# Mini_Converter_2024-05-02.net
KiCad netlist of a schematic drawn in Altium Designer
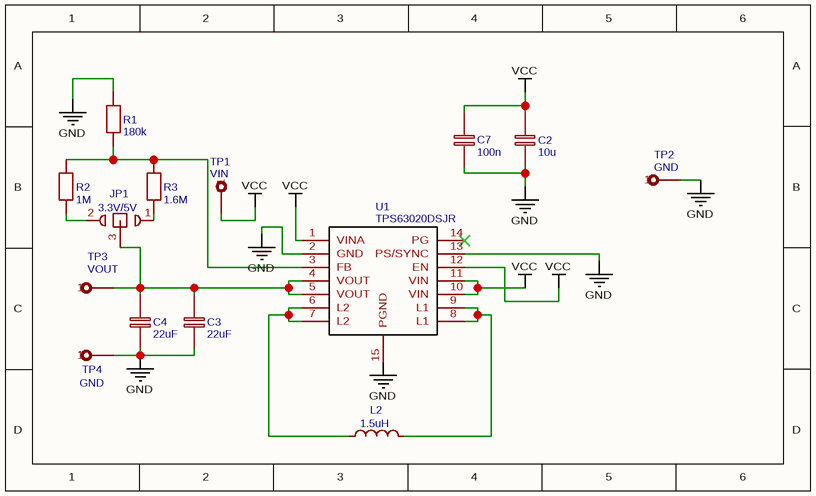
[diagram p0: Mini_Converter_2024-05-02.schdoc]

(export (version "E")
  (design (tool "Eeschema 10.0.6"))
  (components
    (comp (ref "C2")
      (value "10u")
      (fields (field (name "CONTRIBUTOR") "LCEDA_Lib"))
      (libsource (lib "altium-import") (part "root_1_10u_"))
    )
    (comp (ref "C3")
      (value "22uF")
      (fields (field (name "CONTRIBUTOR") "LCEDA_Lib"))
      (libsource (lib "altium-import") (part "root_1_22uF_"))
    )
    (comp (ref "C4")
      (value "22uF")
      (fields (field (name "CONTRIBUTOR") "LCEDA_Lib"))
      (libsource (lib "altium-import") (part "root_1_22uF_"))
    )
    (comp (ref "C7")
      (value "100n")
      (fields (field (name "CONTRIBUTOR") "LCEDA_Lib"))
      (libsource (lib "altium-import") (part "root_1_100n_"))
    )
    (comp (ref "JP1")
      (value "3.3V/5V")
      (fields (field (name "CONTRIBUTOR") "leif"))
      (libsource (lib "altium-import") (part "root_2_3.3V/5V_"))
    )
    (comp (ref "L2")
      (value "1.5uH")
      (fields (field (name "MANUFACTURER PART") "78438336100") (field (name "CONTRIBUTOR") "LCSC"))
      (libsource (lib "altium-import") (part "root_0_1.5uH_"))
    )
    (comp (ref "R1")
      (value "180k")
      (fields (field (name "CONTRIBUTOR") "LCEDA_Lib"))
      (libsource (lib "altium-import") (part "root_1_180k_"))
    )
    (comp (ref "R2")
      (value "1M")
      (fields (field (name "CONTRIBUTOR") "LCEDA_Lib"))
      (libsource (lib "altium-import") (part "root_1_1M_"))
    )
    (comp (ref "R3")
      (value "1.6M")
      (fields (field (name "CONTRIBUTOR") "LCEDA_Lib"))
      (libsource (lib "altium-import") (part "root_1_1.6M_"))
    )
    (comp (ref "TP1") (value "VIN") (libsource (lib "altium-import") (part "root_3_VIN_")))
    (comp (ref "TP2") (value "GND") (libsource (lib "altium-import") (part "root_0_GND_")))
    (comp (ref "TP3") (value "VOUT") (libsource (lib "altium-import") (part "root_0_VOUT_")))
    (comp (ref "TP4") (value "GND") (libsource (lib "altium-import") (part "root_0_GND_")))
    (comp (ref "U1")
      (value "TPS63020DSJR")
      (fields (field (name "MANUFACTURER") "TI(德州仪器)"))
      (libsource (lib "altium-import") (part "root_0_TPS63020DSJR_"))
    )
  )
  (nets
    (net (code "1") (name "GND") (class "Default")
      (node (ref "C2") (pin "1") (pinfunction "1_1") (pintype "passive"))
      (node (ref "C3") (pin "1") (pinfunction "1_1") (pintype "passive"))
      (node (ref "C4") (pin "1") (pinfunction "1_1") (pintype "passive"))
      (node (ref "C7") (pin "1") (pinfunction "1_1") (pintype "passive"))
      (node (ref "R1") (pin "2") (pinfunction "2_2") (pintype "passive"))
      (node (ref "TP2") (pin "1") (pinfunction "1_1") (pintype "passive"))
      (node (ref "TP4") (pin "1") (pinfunction "1_1") (pintype "passive"))
      (node (ref "U1") (pin "13") (pinfunction "PS/SYNC_13") (pintype "passive"))
      (node (ref "U1") (pin "15") (pinfunction "PGND_15") (pintype "passive"))
      (node (ref "U1") (pin "2") (pinfunction "GND_2") (pintype "passive"))
    )
    (net (code "2") (name "Net-(C3-Pad2)") (class "Default")
      (node (ref "C3") (pin "2") (pinfunction "2_2") (pintype "passive"))
      (node (ref "C4") (pin "2") (pinfunction "2_2") (pintype "passive"))
      (node (ref "JP1") (pin "3") (pinfunction "3_3") (pintype "passive"))
      (node (ref "TP3") (pin "1") (pinfunction "1_1") (pintype "passive"))
      (node (ref "U1") (pin "4") (pinfunction "VOUT_4") (pintype "passive"))
      (node (ref "U1") (pin "5") (pinfunction "VOUT_5") (pintype "passive"))
    )
    (net (code "3") (name "Net-(JP1-Pad1)") (class "Default")
      (node (ref "JP1") (pin "1") (pinfunction "1_1") (pintype "passive"))
      (node (ref "R3") (pin "1") (pinfunction "1_1") (pintype "passive"))
    )
    (net (code "4") (name "Net-(JP1-Pad2)") (class "Default")
      (node (ref "JP1") (pin "2") (pinfunction "2_2") (pintype "passive"))
      (node (ref "R2") (pin "1") (pinfunction "1_1") (pintype "passive"))
    )
    (net (code "5") (name "Net-(L2-Pad1)") (class "Default")
      (node (ref "L2") (pin "1") (pinfunction "1_1") (pintype "passive"))
      (node (ref "U1") (pin "6") (pinfunction "L2_6") (pintype "passive"))
      (node (ref "U1") (pin "7") (pinfunction "L2_7") (pintype "passive"))
    )
    (net (code "6") (name "Net-(L2-Pad2)") (class "Default")
      (node (ref "L2") (pin "2") (pinfunction "2_2") (pintype "passive"))
      (node (ref "U1") (pin "8") (pinfunction "L1_8") (pintype "passive"))
      (node (ref "U1") (pin "9") (pinfunction "L1_9") (pintype "passive"))
    )
    (net (code "7") (name "Net-(U1-FB)") (class "Default")
      (node (ref "R1") (pin "1") (pinfunction "1_1") (pintype "passive"))
      (node (ref "R2") (pin "2") (pinfunction "2_2") (pintype "passive"))
      (node (ref "R3") (pin "2") (pinfunction "2_2") (pintype "passive"))
      (node (ref "U1") (pin "3") (pinfunction "FB_3") (pintype "passive"))
    )
    (net (code "8") (name "VCC") (class "Default")
      (node (ref "C2") (pin "2") (pinfunction "2_2") (pintype "passive"))
      (node (ref "C7") (pin "2") (pinfunction "2_2") (pintype "passive"))
      (node (ref "TP1") (pin "1") (pinfunction "1_1") (pintype "passive"))
      (node (ref "U1") (pin "1") (pinfunction "VINA_1") (pintype "passive"))
      (node (ref "U1") (pin "10") (pinfunction "VIN_10") (pintype "passive"))
      (node (ref "U1") (pin "11") (pinfunction "VIN_11") (pintype "passive"))
      (node (ref "U1") (pin "12") (pinfunction "EN_12") (pintype "passive"))
    )
    (net (code "9") (name "unconnected-(U1-PG-Pad14)") (class "Default")
      (node (ref "U1") (pin "14") (pinfunction "PG_14") (pintype "passive+no_connect"))
    )
  )
)
